# SSFocuser-B-DRV8825-KCTW.net
KiCad netlist of a schematic drawn in Altium Designer
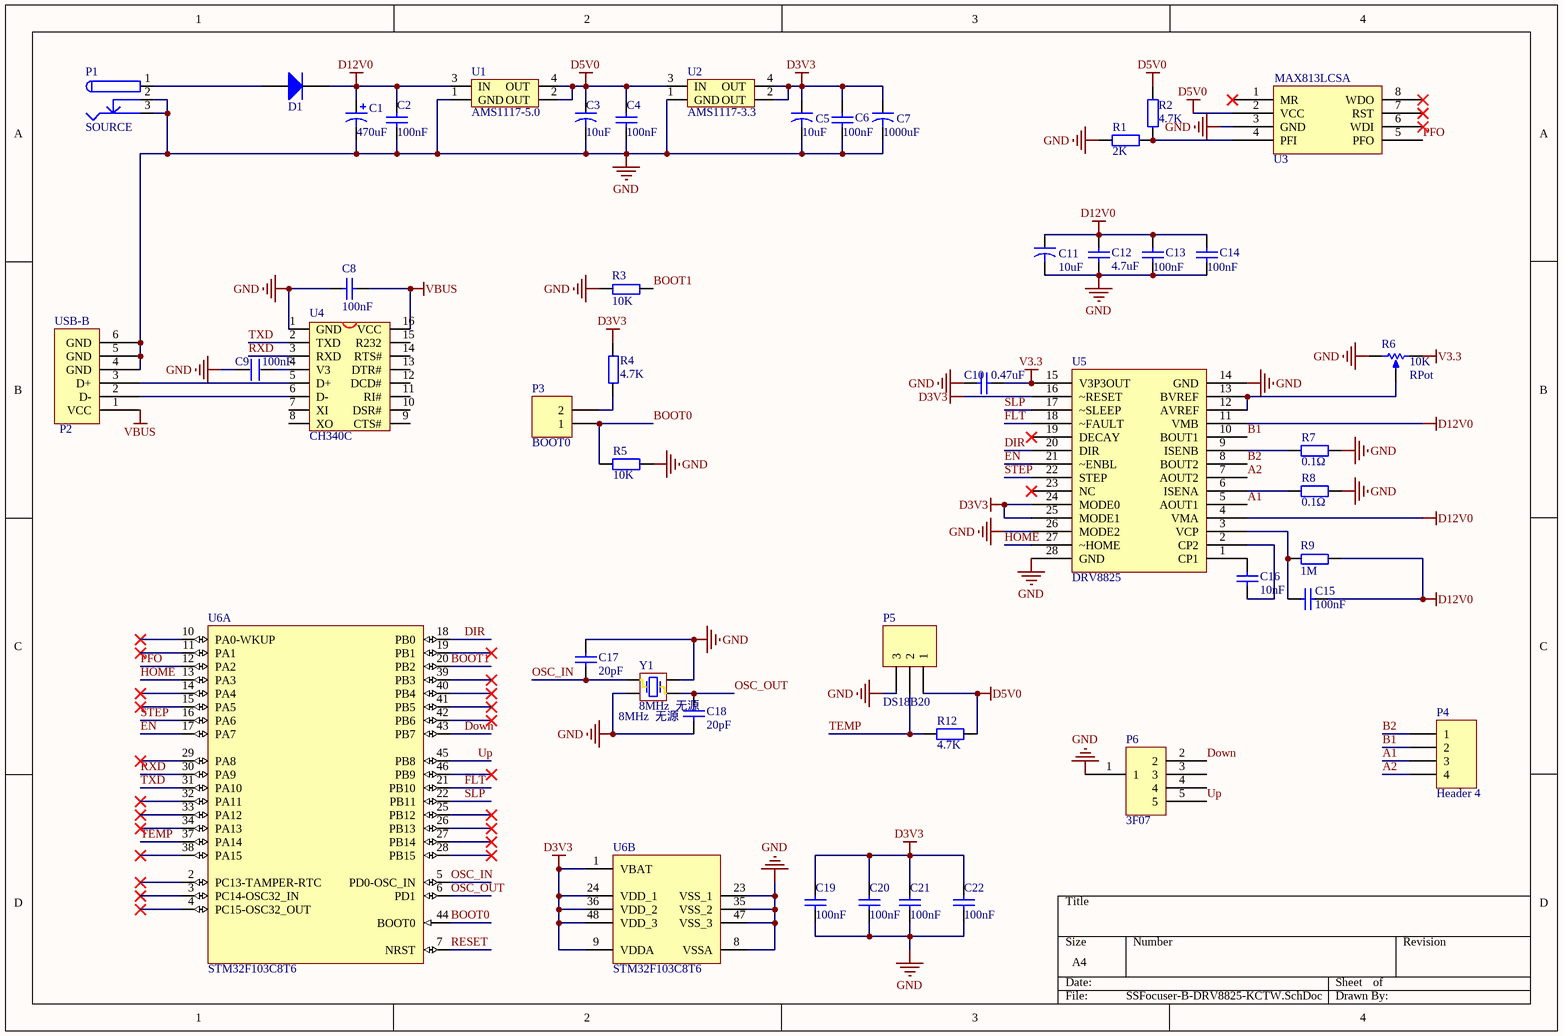
[diagram p0: SSFocuser-B-DRV8825-KCTW.SchDoc]

(export (version "E")
  (design (tool "Eeschema 10.0.6"))
  (components
    (comp (ref "C1")
      (value "470uF")
      (footprint "16V/470U(CD10X10D5)")
      (description "470UF      16V      CD10X10D5")
      (libsource (lib "平台原理图symbol图库V1.0") (part "C470UF016S"))
    )
    (comp (ref "C2")
      (value "100nF")
      (footprint "0603C")
      (description "Capacitor")
      (fields (field (name "PUBLISHER") "Altium Limited"))
      (libsource (lib "Crazy_PCB") (part "Cap"))
    )
    (comp (ref "C3")
      (value "10uF")
      (footprint "3216")
      (fields (field (name "VAULE") "10uF"))
      (libsource (lib "Crazy_PCB") (part "CAP2"))
    )
    (comp (ref "C4")
      (value "100nF")
      (footprint "0603C")
      (description "Capacitor")
      (fields (field (name "PUBLISHER") "Altium Limited"))
      (libsource (lib "Crazy_PCB") (part "Cap"))
    )
    (comp (ref "C5")
      (value "10uF")
      (footprint "3216")
      (fields (field (name "VAULE") "10uF"))
      (libsource (lib "Crazy_PCB") (part "CAP2"))
    )
    (comp (ref "C6")
      (value "100nF")
      (footprint "0603C")
      (description "Capacitor")
      (fields (field (name "PUBLISHER") "Altium Limited"))
      (libsource (lib "Crazy_PCB") (part "Cap"))
    )
    (comp (ref "C7")
      (value "1000uF")
      (footprint "16V/470U(CD10X10D5)")
      (fields (field (name "VAULE") "1000uF"))
      (libsource (lib "Crazy_PCB") (part "CAP2"))
    )
    (comp (ref "C8")
      (value "100nF")
      (footprint "0603C")
      (description "Capacitor")
      (fields (field (name "PUBLISHER") "Altium Limited"))
      (libsource (lib "Crazy_PCB") (part "Cap"))
    )
    (comp (ref "C9")
      (value "100nF")
      (footprint "0603C")
      (libsource (lib "WarShip V3 STM32103封装库") (part "C"))
    )
    (comp (ref "C10")
      (value "0.47uF")
      (footprint "0603C")
      (description "Capacitor")
      (fields (field (name "PUBLISHER") "Altium Limited"))
      (libsource (lib "Crazy_PCB") (part "Cap"))
    )
    (comp (ref "C11")
      (value "10uF")
      (footprint "3216")
      (fields (field (name "VAULE") "10uF"))
      (libsource (lib "Crazy_PCB") (part "CAP2"))
    )
    (comp (ref "C12")
      (value "4.7uF")
      (footprint "1206C")
      (description "Capacitor")
      (fields (field (name "PUBLISHER") "Altium Limited"))
      (libsource (lib "Crazy_PCB") (part "Cap"))
    )
    (comp (ref "C13")
      (value "100nF")
      (footprint "0603C")
      (description "Capacitor")
      (fields (field (name "PUBLISHER") "Altium Limited"))
      (libsource (lib "Crazy_PCB") (part "Cap"))
    )
    (comp (ref "C14")
      (value "100nF")
      (footprint "0603C")
      (description "Capacitor")
      (fields (field (name "PUBLISHER") "Altium Limited"))
      (libsource (lib "Crazy_PCB") (part "Cap"))
    )
    (comp (ref "C15")
      (value "100nF")
      (footprint "0603C")
      (description "Capacitor")
      (fields (field (name "PUBLISHER") "Altium Limited"))
      (libsource (lib "Crazy_PCB") (part "Cap"))
    )
    (comp (ref "C16")
      (value "10nF")
      (footprint "0603C")
      (description "Capacitor")
      (fields (field (name "PUBLISHER") "Altium Limited"))
      (libsource (lib "Crazy_PCB") (part "Cap"))
    )
    (comp (ref "C17")
      (value "20pF")
      (footprint "0603C")
      (description "Capacitor")
      (fields (field (name "PUBLISHER") "Altium Limited"))
      (libsource (lib "JL_SCH") (part "Cap"))
    )
    (comp (ref "C18")
      (value "20pF")
      (footprint "0603C")
      (description "Capacitor")
      (fields (field (name "PUBLISHER") "Altium Limited"))
      (libsource (lib "JL_SCH") (part "Cap"))
    )
    (comp (ref "C19")
      (value "100nF")
      (footprint "0603C")
      (description "Capacitor")
      (fields (field (name "PUBLISHER") "Altium Limited"))
      (libsource (lib "Crazy_PCB") (part "Cap"))
    )
    (comp (ref "C20")
      (value "100nF")
      (footprint "0603C")
      (description "Capacitor")
      (fields (field (name "PUBLISHER") "Altium Limited"))
      (libsource (lib "Crazy_PCB") (part "Cap"))
    )
    (comp (ref "C21")
      (value "100nF")
      (footprint "0603C")
      (description "Capacitor")
      (fields (field (name "PUBLISHER") "Altium Limited"))
      (libsource (lib "Crazy_PCB") (part "Cap"))
    )
    (comp (ref "C22")
      (value "100nF")
      (footprint "0603C")
      (description "Capacitor")
      (fields (field (name "PUBLISHER") "Altium Limited"))
      (libsource (lib "Crazy_PCB") (part "Cap"))
    )
    (comp (ref "D1")
      (value "M7")
      (footprint "DO-214AC")
      (description "High Conductance Fast Diode")
      (fields (field (name "PUBLISHER") "Altium Limited"))
      (libsource (lib "Crazy_PCB") (part "Diode"))
    )
    (comp (ref "P1")
      (value "SOURCE")
      (footprint "DC005")
      (fields (field (name "PUBLISHER") "Altium Limited"))
      (libsource (lib "Crazy_PCB") (part "SOURCE"))
    )
    (comp (ref "P2") (value "USB-B") (footprint "USB-B") (libsource (lib "DX") (part "USB-B")))
    (comp (ref "P3")
      (value "BOOT0")
      (footprint "HDR1X2")
      (description "Header, 2-Pin")
      (fields (field (name "PUBLISHER") "Altium Limited"))
      (libsource (lib "Miscellaneous Connectors") (part "MHDR1X2"))
    )
    (comp (ref "P4")
      (value "Header 4")
      (footprint "XH_4_V")
      (description "Header, 4-Pin")
      (fields (field (name "PUBLISHER") "Altium Limited"))
      (libsource (lib "Miscellaneous Connectors") (part "Header 4"))
    )
    (comp (ref "P5")
      (value "DS18B20")
      (footprint "TO-92B")
      (description "Header, 3-Pin")
      (fields (field (name "PUBLISHER") "Altium Limited"))
      (libsource (lib "Miscellaneous Connectors") (part "Header 3"))
    )
    (comp (ref "P6")
      (value "3F07")
      (footprint "3F07")
      (description "EarPhone3.5")
      (libsource (lib "SS") (part "3F07"))
    )
    (comp (ref "R1")
      (value "2K")
      (footprint "0603R")
      (description "Resistor")
      (fields (field (name "PUBLISHER") "Altium Limited"))
      (libsource (lib "") (part "RES_1"))
    )
    (comp (ref "R2")
      (value "4.7K")
      (footprint "0603R")
      (description "Resistor")
      (fields (field (name "PUBLISHER") "Altium Limited"))
      (libsource (lib "") (part "RES_2"))
    )
    (comp (ref "R3") (value "10K") (footprint "0603R") (libsource (lib "WarShip V3 STM32103封装库") (part "R")))
    (comp (ref "R4") (value "4.7K") (footprint "0603R") (libsource (lib "WarShip V3 STM32103封装库") (part "R")))
    (comp (ref "R5")
      (value "10K")
      (footprint "0603R")
      (description "Resistor")
      (fields (field (name "PUBLISHER") "Altium Limited"))
      (libsource (lib "Crazy_PCB") (part "RES"))
    )
    (comp (ref "R6")
      (value "RPot")
      (footprint "VR_SMD")
      (description "Potentiometer")
      (fields (field (name "ALTIUM_VALUE") "10K") (field (name "PUBLISHER") "Altium Limited"))
      (libsource (lib "Miscellaneous Devices") (part "RPot"))
    )
    (comp (ref "R7")
      (value "0.1Ω")
      (footprint "1206R")
      (description "Resistor")
      (fields (field (name "PUBLISHER") "Altium Limited"))
      (libsource (lib "") (part "RES_1"))
    )
    (comp (ref "R8")
      (value "0.1Ω")
      (footprint "1206R")
      (description "Resistor")
      (fields (field (name "PUBLISHER") "Altium Limited"))
      (libsource (lib "") (part "RES_1"))
    )
    (comp (ref "R9") (value "1M") (footprint "0603R") (libsource (lib "WarShip V3 STM32103封装库") (part "R")))
    (comp (ref "R12")
      (value "4.7K")
      (footprint "0603R")
      (description "Resistor")
      (fields (field (name "PUBLISHER") "Altium Limited"))
      (libsource (lib "Crazy_PCB") (part "RES"))
    )
    (comp (ref "U1")
      (value "AMS1117-5.0")
      (footprint "SOT223")
      (libsource (lib "MiniSTM32 V3.0封装库") (part "AMS1117"))
    )
    (comp (ref "U2")
      (value "AMS1117-3.3")
      (footprint "SOT223")
      (libsource (lib "MiniSTM32 V3.0封装库") (part "AMS1117"))
    )
    (comp (ref "U3") (value "MAX813LCSA") (footprint "SOP-8") (libsource (lib "DX") (part "MAX813L")))
    (comp (ref "U4")
      (value "CH340C")
      (footprint "SO-16")
      (description "USB2UART")
      (libsource (lib "WarShip V3 STM32103封装库") (part "CH340G"))
    )
    (comp (ref "U5") (value "DRV8825") (footprint "HTSSOP") (libsource (lib "MySchlib") (part "DRV8825")))
    (comp (ref "U6")
      (value "STM32F103C8T6")
      (footprint "LQFP48_N")
      (libsource (lib "STMicroelectronics STM32 F1") (part "STM32F103C8T6"))
    )
    (comp (ref "Y1")
      (value "8MHz  无源")
      (footprint "X3225")
      (description "Crystal Oscillator")
      (fields (field (name "ALTIUM_VALUE") "8MHz  无源") (field (name "PUBLISHER") "Altium Limited"))
      (libsource (lib "JL_SCH") (part "XTAL_1"))
    )
  )
  (nets
    (net (code "1") (name "/A1") (class "Default")
      (node (ref "P4") (pin "3") (pinfunction "3_3") (pintype "passive"))
      (node (ref "U5") (pin "5") (pinfunction "AOUT1_5") (pintype "passive"))
    )
    (net (code "2") (name "/A2") (class "Default")
      (node (ref "P4") (pin "4") (pinfunction "4_4") (pintype "passive"))
      (node (ref "U5") (pin "7") (pinfunction "AOUT2_7") (pintype "passive"))
    )
    (net (code "3") (name "/B1") (class "Default")
      (node (ref "P4") (pin "2") (pinfunction "2_2") (pintype "passive"))
      (node (ref "U5") (pin "10") (pinfunction "BOUT1_10") (pintype "passive"))
    )
    (net (code "4") (name "/B2") (class "Default")
      (node (ref "P4") (pin "1") (pinfunction "1_1") (pintype "passive"))
      (node (ref "U5") (pin "8") (pinfunction "BOUT2_8") (pintype "passive"))
    )
    (net (code "5") (name "/BOOT0") (class "Default")
      (node (ref "P3") (pin "1") (pinfunction "1_1") (pintype "passive"))
      (node (ref "R5") (pin "1") (pinfunction "1_1") (pintype "passive"))
      (node (ref "U6") (pin "44") (pinfunction "BOOT0_44") (pintype "input"))
    )
    (net (code "6") (name "/BOOT1") (class "Default")
      (node (ref "R3") (pin "2") (pintype "passive"))
      (node (ref "U6") (pin "20") (pinfunction "PB2_20") (pintype "bidirectional"))
    )
    (net (code "7") (name "/DIR") (class "Default")
      (node (ref "U5") (pin "20") (pinfunction "DIR_20") (pintype "passive"))
      (node (ref "U6") (pin "18") (pinfunction "PB0_18") (pintype "bidirectional"))
    )
    (net (code "8") (name "/Down") (class "Default")
      (node (ref "P6") (pin "2") (pinfunction "2_2") (pintype "passive"))
      (node (ref "U6") (pin "43") (pinfunction "PB7_43") (pintype "bidirectional"))
    )
    (net (code "9") (name "/EN") (class "Default")
      (node (ref "U5") (pin "21") (pinfunction "~ENBL_21") (pintype "passive"))
      (node (ref "U6") (pin "17") (pinfunction "PA7_17") (pintype "bidirectional"))
    )
    (net (code "10") (name "/FLT") (class "Default")
      (node (ref "U5") (pin "18") (pinfunction "~FAULT_18") (pintype "passive"))
      (node (ref "U6") (pin "21") (pinfunction "PB10_21") (pintype "bidirectional"))
    )
    (net (code "11") (name "/HOME") (class "Default")
      (node (ref "U5") (pin "27") (pinfunction "~HOME_27") (pintype "passive"))
      (node (ref "U6") (pin "13") (pinfunction "PA3_13") (pintype "bidirectional"))
    )
    (net (code "12") (name "/OSC_IN") (class "Default")
      (node (ref "C17") (pin "1") (pinfunction "1_1") (pintype "passive"))
      (node (ref "U6") (pin "5") (pinfunction "PD0-OSC_IN_5") (pintype "bidirectional"))
      (node (ref "Y1") (pin "1") (pinfunction "OSC1_1") (pintype "passive"))
    )
    (net (code "13") (name "/OSC_OUT") (class "Default")
      (node (ref "C18") (pin "1") (pinfunction "1_1") (pintype "passive"))
      (node (ref "U6") (pin "6") (pinfunction "PD1_6") (pintype "bidirectional"))
      (node (ref "Y1") (pin "3") (pinfunction "OSC2_3") (pintype "passive"))
    )
    (net (code "14") (name "/PFO") (class "Default")
      (node (ref "U3") (pin "5") (pinfunction "PFO_5") (pintype "passive"))
      (node (ref "U6") (pin "12") (pinfunction "PA2_12") (pintype "bidirectional"))
    )
    (net (code "15") (name "/RESET") (class "Default")
      (node (ref "U6") (pin "7") (pinfunction "NRST_7") (pintype "bidirectional"))
    )
    (net (code "16") (name "/RXD") (class "Default")
      (node (ref "U4") (pin "3") (pinfunction "RXD_3") (pintype "passive"))
      (node (ref "U6") (pin "30") (pinfunction "PA9_30") (pintype "bidirectional"))
    )
    (net (code "17") (name "/SLP") (class "Default")
      (node (ref "U5") (pin "17") (pinfunction "~SLEEP_17") (pintype "passive"))
      (node (ref "U6") (pin "22") (pinfunction "PB11_22") (pintype "bidirectional"))
    )
    (net (code "18") (name "/STEP") (class "Default")
      (node (ref "U5") (pin "22") (pinfunction "STEP_22") (pintype "passive"))
      (node (ref "U6") (pin "16") (pinfunction "PA6_16") (pintype "bidirectional"))
    )
    (net (code "19") (name "/TEMP") (class "Default")
      (node (ref "P5") (pin "2") (pinfunction "2_2") (pintype "passive"))
      (node (ref "R12") (pin "1") (pinfunction "1_1") (pintype "passive"))
      (node (ref "U6") (pin "37") (pinfunction "PA14_37") (pintype "bidirectional"))
    )
    (net (code "20") (name "/TXD") (class "Default")
      (node (ref "U4") (pin "2") (pinfunction "TXD_2") (pintype "passive"))
      (node (ref "U6") (pin "31") (pinfunction "PA10_31") (pintype "bidirectional"))
    )
    (net (code "21") (name "/Up") (class "Default")
      (node (ref "P6") (pin "5") (pinfunction "5_5") (pintype "passive"))
      (node (ref "U6") (pin "45") (pinfunction "PB8_45") (pintype "bidirectional"))
    )
    (net (code "22") (name "D3V3") (class "Default")
      (node (ref "C19") (pin "2") (pinfunction "2_2") (pintype "passive"))
      (node (ref "C20") (pin "2") (pinfunction "2_2") (pintype "passive"))
      (node (ref "C21") (pin "2") (pinfunction "2_2") (pintype "passive"))
      (node (ref "C22") (pin "2") (pinfunction "2_2") (pintype "passive"))
      (node (ref "C5") (pin "1") (pinfunction "1_1") (pintype "passive"))
      (node (ref "C6") (pin "2") (pinfunction "2_2") (pintype "passive"))
      (node (ref "C7") (pin "1") (pinfunction "1_1") (pintype "passive"))
      (node (ref "R4") (pin "2") (pintype "passive"))
      (node (ref "U2") (pin "2") (pinfunction "OUT_2") (pintype "passive"))
      (node (ref "U2") (pin "4") (pinfunction "OUT_4") (pintype "passive"))
      (node (ref "U5") (pin "16") (pinfunction "~RESET_16") (pintype "passive"))
      (node (ref "U5") (pin "24") (pinfunction "MODE0_24") (pintype "passive"))
      (node (ref "U5") (pin "25") (pinfunction "MODE1_25") (pintype "passive"))
      (node (ref "U6") (pin "1") (pinfunction "VBAT_1") (pintype "power_in"))
      (node (ref "U6") (pin "24") (pinfunction "VDD_1_24") (pintype "power_in"))
      (node (ref "U6") (pin "36") (pinfunction "VDD_2_36") (pintype "power_in"))
      (node (ref "U6") (pin "48") (pinfunction "VDD_3_48") (pintype "power_in"))
      (node (ref "U6") (pin "9") (pinfunction "VDDA_9") (pintype "power_in"))
    )
    (net (code "23") (name "D5V0") (class "Default")
      (node (ref "C3") (pin "1") (pinfunction "1_1") (pintype "passive"))
      (node (ref "C4") (pin "2") (pinfunction "2_2") (pintype "passive"))
      (node (ref "P5") (pin "1") (pinfunction "1_1") (pintype "passive"))
      (node (ref "R12") (pin "2") (pinfunction "2_2") (pintype "passive"))
      (node (ref "R2") (pin "2") (pinfunction "2_2") (pintype "passive"))
      (node (ref "U1") (pin "2") (pinfunction "OUT_2") (pintype "passive"))
      (node (ref "U1") (pin "4") (pinfunction "OUT_4") (pintype "passive"))
      (node (ref "U2") (pin "3") (pinfunction "IN_3") (pintype "passive"))
      (node (ref "U3") (pin "2") (pinfunction "VCC_2") (pintype "passive"))
    )
    (net (code "24") (name "D12V0") (class "Default")
      (node (ref "C1") (pin "1") (pinfunction "1_1") (pintype "passive"))
      (node (ref "C11") (pin "1") (pinfunction "1_1") (pintype "passive"))
      (node (ref "C12") (pin "1") (pinfunction "1_1") (pintype "passive"))
      (node (ref "C13") (pin "2") (pinfunction "2_2") (pintype "passive"))
      (node (ref "C14") (pin "2") (pinfunction "2_2") (pintype "passive"))
      (node (ref "C15") (pin "1") (pinfunction "1_1") (pintype "passive"))
      (node (ref "C2") (pin "2") (pinfunction "2_2") (pintype "passive"))
      (node (ref "D1") (pin "2") (pinfunction "K_2") (pintype "passive"))
      (node (ref "R9") (pin "2") (pintype "passive"))
      (node (ref "U1") (pin "3") (pinfunction "IN_3") (pintype "passive"))
      (node (ref "U5") (pin "11") (pinfunction "VMB_11") (pintype "passive"))
      (node (ref "U5") (pin "4") (pinfunction "VMA_4") (pintype "passive"))
    )
    (net (code "25") (name "GND") (class "Default")
      (node (ref "C1") (pin "2") (pinfunction "2_2") (pintype "passive"))
      (node (ref "C10") (pin "1") (pinfunction "1_1") (pintype "passive"))
      (node (ref "C11") (pin "2") (pinfunction "2_2") (pintype "passive"))
      (node (ref "C12") (pin "2") (pinfunction "2_2") (pintype "passive"))
      (node (ref "C13") (pin "1") (pinfunction "1_1") (pintype "passive"))
      (node (ref "C14") (pin "1") (pinfunction "1_1") (pintype "passive"))
      (node (ref "C17") (pin "2") (pinfunction "2_2") (pintype "passive"))
      (node (ref "C18") (pin "2") (pinfunction "2_2") (pintype "passive"))
      (node (ref "C19") (pin "1") (pinfunction "1_1") (pintype "passive"))
      (node (ref "C2") (pin "1") (pinfunction "1_1") (pintype "passive"))
      (node (ref "C20") (pin "1") (pinfunction "1_1") (pintype "passive"))
      (node (ref "C21") (pin "1") (pinfunction "1_1") (pintype "passive"))
      (node (ref "C22") (pin "1") (pinfunction "1_1") (pintype "passive"))
      (node (ref "C3") (pin "2") (pinfunction "2_2") (pintype "passive"))
      (node (ref "C4") (pin "1") (pinfunction "1_1") (pintype "passive"))
      (node (ref "C5") (pin "2") (pinfunction "2_2") (pintype "passive"))
      (node (ref "C6") (pin "1") (pinfunction "1_1") (pintype "passive"))
      (node (ref "C7") (pin "2") (pinfunction "2_2") (pintype "passive"))
      (node (ref "C8") (pin "1") (pinfunction "1_1") (pintype "passive"))
      (node (ref "C9") (pin "1") (pintype "passive"))
      (node (ref "P1") (pin "2") (pinfunction "2_2") (pintype "power_in"))
      (node (ref "P1") (pin "3") (pinfunction "3_3") (pintype "power_in"))
      (node (ref "P2") (pin "4") (pinfunction "GND_4") (pintype "passive"))
      (node (ref "P2") (pin "5") (pinfunction "GND_5") (pintype "passive"))
      (node (ref "P2") (pin "6") (pinfunction "GND_6") (pintype "passive"))
      (node (ref "P5") (pin "3") (pinfunction "3_3") (pintype "passive"))
      (node (ref "P6") (pin "1") (pinfunction "1_1") (pintype "passive"))
      (node (ref "R1") (pin "2") (pinfunction "2_2") (pintype "passive"))
      (node (ref "R3") (pin "1") (pintype "passive"))
      (node (ref "R5") (pin "2") (pinfunction "2_2") (pintype "passive"))
      (node (ref "R6") (pin "1") (pinfunction "TOP_1") (pintype "passive"))
      (node (ref "R7") (pin "1") (pinfunction "1_1") (pintype "passive"))
      (node (ref "R8") (pin "1") (pinfunction "1_1") (pintype "passive"))
      (node (ref "U1") (pin "1") (pinfunction "GND_1") (pintype "passive"))
      (node (ref "U2") (pin "1") (pinfunction "GND_1") (pintype "passive"))
      (node (ref "U3") (pin "3") (pinfunction "GND_3") (pintype "passive"))
      (node (ref "U4") (pin "1") (pinfunction "GND_1") (pintype "passive"))
      (node (ref "U5") (pin "14") (pinfunction "GND_14") (pintype "passive"))
      (node (ref "U5") (pin "26") (pinfunction "MODE2_26") (pintype "passive"))
      (node (ref "U5") (pin "28") (pinfunction "GND_28") (pintype "passive"))
      (node (ref "U6") (pin "23") (pinfunction "VSS_1_23") (pintype "power_in"))
      (node (ref "U6") (pin "35") (pinfunction "VSS_2_35") (pintype "power_in"))
      (node (ref "U6") (pin "47") (pinfunction "VSS_3_47") (pintype "power_in"))
      (node (ref "U6") (pin "8") (pinfunction "VSSA_8") (pintype "power_in"))
      (node (ref "Y1") (pin "2") (pinfunction "NA_2") (pintype "passive"))
      (node (ref "Y1") (pin "4") (pinfunction "NA_4") (pintype "passive"))
    )
    (net (code "26") (name "Net-(D1-A)") (class "Default")
      (node (ref "D1") (pin "1") (pinfunction "A_1") (pintype "passive"))
      (node (ref "P1") (pin "1") (pinfunction "1_1") (pintype "power_in"))
    )
    (net (code "27") (name "Net-(P2-D+)") (class "Default")
      (node (ref "P2") (pin "3") (pinfunction "D+_3") (pintype "passive"))
      (node (ref "U4") (pin "5") (pinfunction "D+_5") (pintype "passive"))
    )
    (net (code "28") (name "Net-(P2-D-)") (class "Default")
      (node (ref "P2") (pin "2") (pinfunction "D-_2") (pintype "passive"))
      (node (ref "U4") (pin "6") (pinfunction "D-_6") (pintype "passive"))
    )
    (net (code "29") (name "Net-(P3-Pad2)") (class "Default")
      (node (ref "P3") (pin "2") (pinfunction "2_2") (pintype "passive"))
      (node (ref "R4") (pin "1") (pintype "passive"))
    )
    (net (code "30") (name "Net-(R6-TAP)") (class "Default")
      (node (ref "R6") (pin "3") (pinfunction "TAP_3") (pintype "passive"))
      (node (ref "U5") (pin "12") (pinfunction "AVREF_12") (pintype "passive"))
      (node (ref "U5") (pin "13") (pinfunction "BVREF_13") (pintype "passive"))
    )
    (net (code "31") (name "Net-(U3-PFI)") (class "Default")
      (node (ref "R1") (pin "1") (pinfunction "1_1") (pintype "passive"))
      (node (ref "R2") (pin "1") (pinfunction "1_1") (pintype "passive"))
      (node (ref "U3") (pin "4") (pinfunction "PFI_4") (pintype "passive"))
    )
    (net (code "32") (name "Net-(U4-V3)") (class "Default")
      (node (ref "C9") (pin "2") (pintype "passive"))
      (node (ref "U4") (pin "4") (pinfunction "V3_4") (pintype "passive"))
    )
    (net (code "33") (name "Net-(U5-CP1)") (class "Default")
      (node (ref "C16") (pin "2") (pinfunction "2_2") (pintype "passive"))
      (node (ref "U5") (pin "1") (pinfunction "CP1_1") (pintype "passive"))
    )
    (net (code "34") (name "Net-(U5-CP2)") (class "Default")
      (node (ref "C16") (pin "1") (pinfunction "1_1") (pintype "passive"))
      (node (ref "U5") (pin "2") (pinfunction "CP2_2") (pintype "passive"))
    )
    (net (code "35") (name "Net-(U5-ISENA)") (class "Default")
      (node (ref "R8") (pin "2") (pinfunction "2_2") (pintype "passive"))
      (node (ref "U5") (pin "6") (pinfunction "ISENA_6") (pintype "passive"))
    )
    (net (code "36") (name "Net-(U5-ISENB)") (class "Default")
      (node (ref "R7") (pin "2") (pinfunction "2_2") (pintype "passive"))
      (node (ref "U5") (pin "9") (pinfunction "ISENB_9") (pintype "passive"))
    )
    (net (code "37") (name "Net-(U5-VCP)") (class "Default")
      (node (ref "C15") (pin "2") (pinfunction "2_2") (pintype "passive"))
      (node (ref "R9") (pin "1") (pintype "passive"))
      (node (ref "U5") (pin "3") (pinfunction "VCP_3") (pintype "passive"))
    )
    (net (code "38") (name "V3.3") (class "Default")
      (node (ref "C10") (pin "2") (pinfunction "2_2") (pintype "passive"))
      (node (ref "R6") (pin "2") (pinfunction "BOT_2") (pintype "passive"))
      (node (ref "U5") (pin "15") (pinfunction "V3P3OUT_15") (pintype "passive"))
    )
    (net (code "39") (name "VBUS") (class "Default")
      (node (ref "C8") (pin "2") (pinfunction "2_2") (pintype "passive"))
      (node (ref "P2") (pin "1") (pinfunction "VCC_1") (pintype "passive"))
      (node (ref "U4") (pin "16") (pinfunction "VCC_16") (pintype "passive"))
    )
    (net (code "40") (name "unconnected-(P6-Pad3)") (class "Default")
      (node (ref "P6") (pin "3") (pinfunction "3_3") (pintype "passive"))
    )
    (net (code "41") (name "unconnected-(P6-Pad4)") (class "Default")
      (node (ref "P6") (pin "4") (pinfunction "4_4") (pintype "passive"))
    )
    (net (code "42") (name "unconnected-(U3-MR-Pad1)") (class "Default")
      (node (ref "U3") (pin "1") (pinfunction "MR_1") (pintype "passive+no_connect"))
    )
    (net (code "43") (name "unconnected-(U3-RST-Pad7)") (class "Default")
      (node (ref "U3") (pin "7") (pinfunction "RST_7") (pintype "passive+no_connect"))
    )
    (net (code "44") (name "unconnected-(U3-WDI-Pad6)") (class "Default")
      (node (ref "U3") (pin "6") (pinfunction "WDI_6") (pintype "passive+no_connect"))
    )
    (net (code "45") (name "unconnected-(U3-WDO-Pad8)") (class "Default")
      (node (ref "U3") (pin "8") (pinfunction "WDO_8") (pintype "passive+no_connect"))
    )
    (net (code "46") (name "unconnected-(U4-CTS#-Pad9)") (class "Default")
      (node (ref "U4") (pin "9") (pinfunction "CTS#_9") (pintype "passive"))
    )
    (net (code "47") (name "unconnected-(U4-DCD#-Pad12)") (class "Default")
      (node (ref "U4") (pin "12") (pinfunction "DCD#_12") (pintype "passive"))
    )
    (net (code "48") (name "unconnected-(U4-DSR#-Pad10)") (class "Default")
      (node (ref "U4") (pin "10") (pinfunction "DSR#_10") (pintype "passive"))
    )
    (net (code "49") (name "unconnected-(U4-DTR#-Pad13)") (class "Default")
      (node (ref "U4") (pin "13") (pinfunction "DTR#_13") (pintype "passive"))
    )
    (net (code "50") (name "unconnected-(U4-R232-Pad15)") (class "Default")
      (node (ref "U4") (pin "15") (pinfunction "R232_15") (pintype "passive"))
    )
    (net (code "51") (name "unconnected-(U4-RI#-Pad11)") (class "Default")
      (node (ref "U4") (pin "11") (pinfunction "RI#_11") (pintype "passive"))
    )
    (net (code "52") (name "unconnected-(U4-RTS#-Pad14)") (class "Default")
      (node (ref "U4") (pin "14") (pinfunction "RTS#_14") (pintype "passive"))
    )
    (net (code "53") (name "unconnected-(U4-XI-Pad7)") (class "Default")
      (node (ref "U4") (pin "7") (pinfunction "XI_7") (pintype "passive"))
    )
    (net (code "54") (name "unconnected-(U4-XO-Pad8)") (class "Default")
      (node (ref "U4") (pin "8") (pinfunction "XO_8") (pintype "passive"))
    )
    (net (code "55") (name "unconnected-(U5-DECAY-Pad19)") (class "Default")
      (node (ref "U5") (pin "19") (pinfunction "DECAY_19") (pintype "passive+no_connect"))
    )
    (net (code "56") (name "unconnected-(U5-NC-Pad23)") (class "Default")
      (node (ref "U5") (pin "23") (pinfunction "NC_23") (pintype "passive+no_connect"))
    )
    (net (code "57") (name "unconnected-(U6A-PA0-WKUP-Pad10)") (class "Default")
      (node (ref "U6") (pin "10") (pinfunction "PA0-WKUP_10") (pintype "bidirectional+no_connect"))
    )
    (net (code "58") (name "unconnected-(U6A-PA1-Pad11)") (class "Default")
      (node (ref "U6") (pin "11") (pinfunction "PA1_11") (pintype "bidirectional+no_connect"))
    )
    (net (code "59") (name "unconnected-(U6A-PA4-Pad14)") (class "Default")
      (node (ref "U6") (pin "14") (pinfunction "PA4_14") (pintype "bidirectional+no_connect"))
    )
    (net (code "60") (name "unconnected-(U6A-PA5-Pad15)") (class "Default")
      (node (ref "U6") (pin "15") (pinfunction "PA5_15") (pintype "bidirectional+no_connect"))
    )
    (net (code "61") (name "unconnected-(U6A-PA8-Pad29)") (class "Default")
      (node (ref "U6") (pin "29") (pinfunction "PA8_29") (pintype "bidirectional+no_connect"))
    )
    (net (code "62") (name "unconnected-(U6A-PA11-Pad32)") (class "Default")
      (node (ref "U6") (pin "32") (pinfunction "PA11_32") (pintype "bidirectional+no_connect"))
    )
    (net (code "63") (name "unconnected-(U6A-PA12-Pad33)") (class "Default")
      (node (ref "U6") (pin "33") (pinfunction "PA12_33") (pintype "bidirectional+no_connect"))
    )
    (net (code "64") (name "unconnected-(U6A-PA13-Pad34)") (class "Default")
      (node (ref "U6") (pin "34") (pinfunction "PA13_34") (pintype "bidirectional+no_connect"))
    )
    (net (code "65") (name "unconnected-(U6A-PA15-Pad38)") (class "Default")
      (node (ref "U6") (pin "38") (pinfunction "PA15_38") (pintype "bidirectional+no_connect"))
    )
    (net (code "66") (name "unconnected-(U6A-PB1-Pad19)") (class "Default")
      (node (ref "U6") (pin "19") (pinfunction "PB1_19") (pintype "bidirectional+no_connect"))
    )
    (net (code "67") (name "unconnected-(U6A-PB3-Pad39)") (class "Default")
      (node (ref "U6") (pin "39") (pinfunction "PB3_39") (pintype "bidirectional+no_connect"))
    )
    (net (code "68") (name "unconnected-(U6A-PB4-Pad40)") (class "Default")
      (node (ref "U6") (pin "40") (pinfunction "PB4_40") (pintype "bidirectional+no_connect"))
    )
    (net (code "69") (name "unconnected-(U6A-PB5-Pad41)") (class "Default")
      (node (ref "U6") (pin "41") (pinfunction "PB5_41") (pintype "bidirectional+no_connect"))
    )
    (net (code "70") (name "unconnected-(U6A-PB6-Pad42)") (class "Default")
      (node (ref "U6") (pin "42") (pinfunction "PB6_42") (pintype "bidirectional+no_connect"))
    )
    (net (code "71") (name "unconnected-(U6A-PB9-Pad46)") (class "Default")
      (node (ref "U6") (pin "46") (pinfunction "PB9_46") (pintype "bidirectional+no_connect"))
    )
    (net (code "72") (name "unconnected-(U6A-PB12-Pad25)") (class "Default")
      (node (ref "U6") (pin "25") (pinfunction "PB12_25") (pintype "bidirectional+no_connect"))
    )
    (net (code "73") (name "unconnected-(U6A-PB13-Pad26)") (class "Default")
      (node (ref "U6") (pin "26") (pinfunction "PB13_26") (pintype "bidirectional+no_connect"))
    )
    (net (code "74") (name "unconnected-(U6A-PB14-Pad27)") (class "Default")
      (node (ref "U6") (pin "27") (pinfunction "PB14_27") (pintype "bidirectional+no_connect"))
    )
    (net (code "75") (name "unconnected-(U6A-PB15-Pad28)") (class "Default")
      (node (ref "U6") (pin "28") (pinfunction "PB15_28") (pintype "bidirectional+no_connect"))
    )
    (net (code "76") (name "unconnected-(U6A-PC13-TAMPER-RTC-Pad2)") (class "Default")
      (node (ref "U6") (pin "2") (pinfunction "PC13-TAMPER-RTC_2") (pintype "bidirectional+no_connect"))
    )
    (net (code "77") (name "unconnected-(U6A-PC14-OSC32_IN-Pad3)") (class "Default")
      (node (ref "U6") (pin "3") (pinfunction "PC14-OSC32_IN_3") (pintype "bidirectional+no_connect"))
    )
    (net (code "78") (name "unconnected-(U6A-PC15-OSC32_OUT-Pad4)") (class "Default")
      (node (ref "U6") (pin "4") (pinfunction "PC15-OSC32_OUT_4") (pintype "bidirectional+no_connect"))
    )
  )
)
